# dorthy.net
KiCad netlist of a schematic drawn in EAGLE
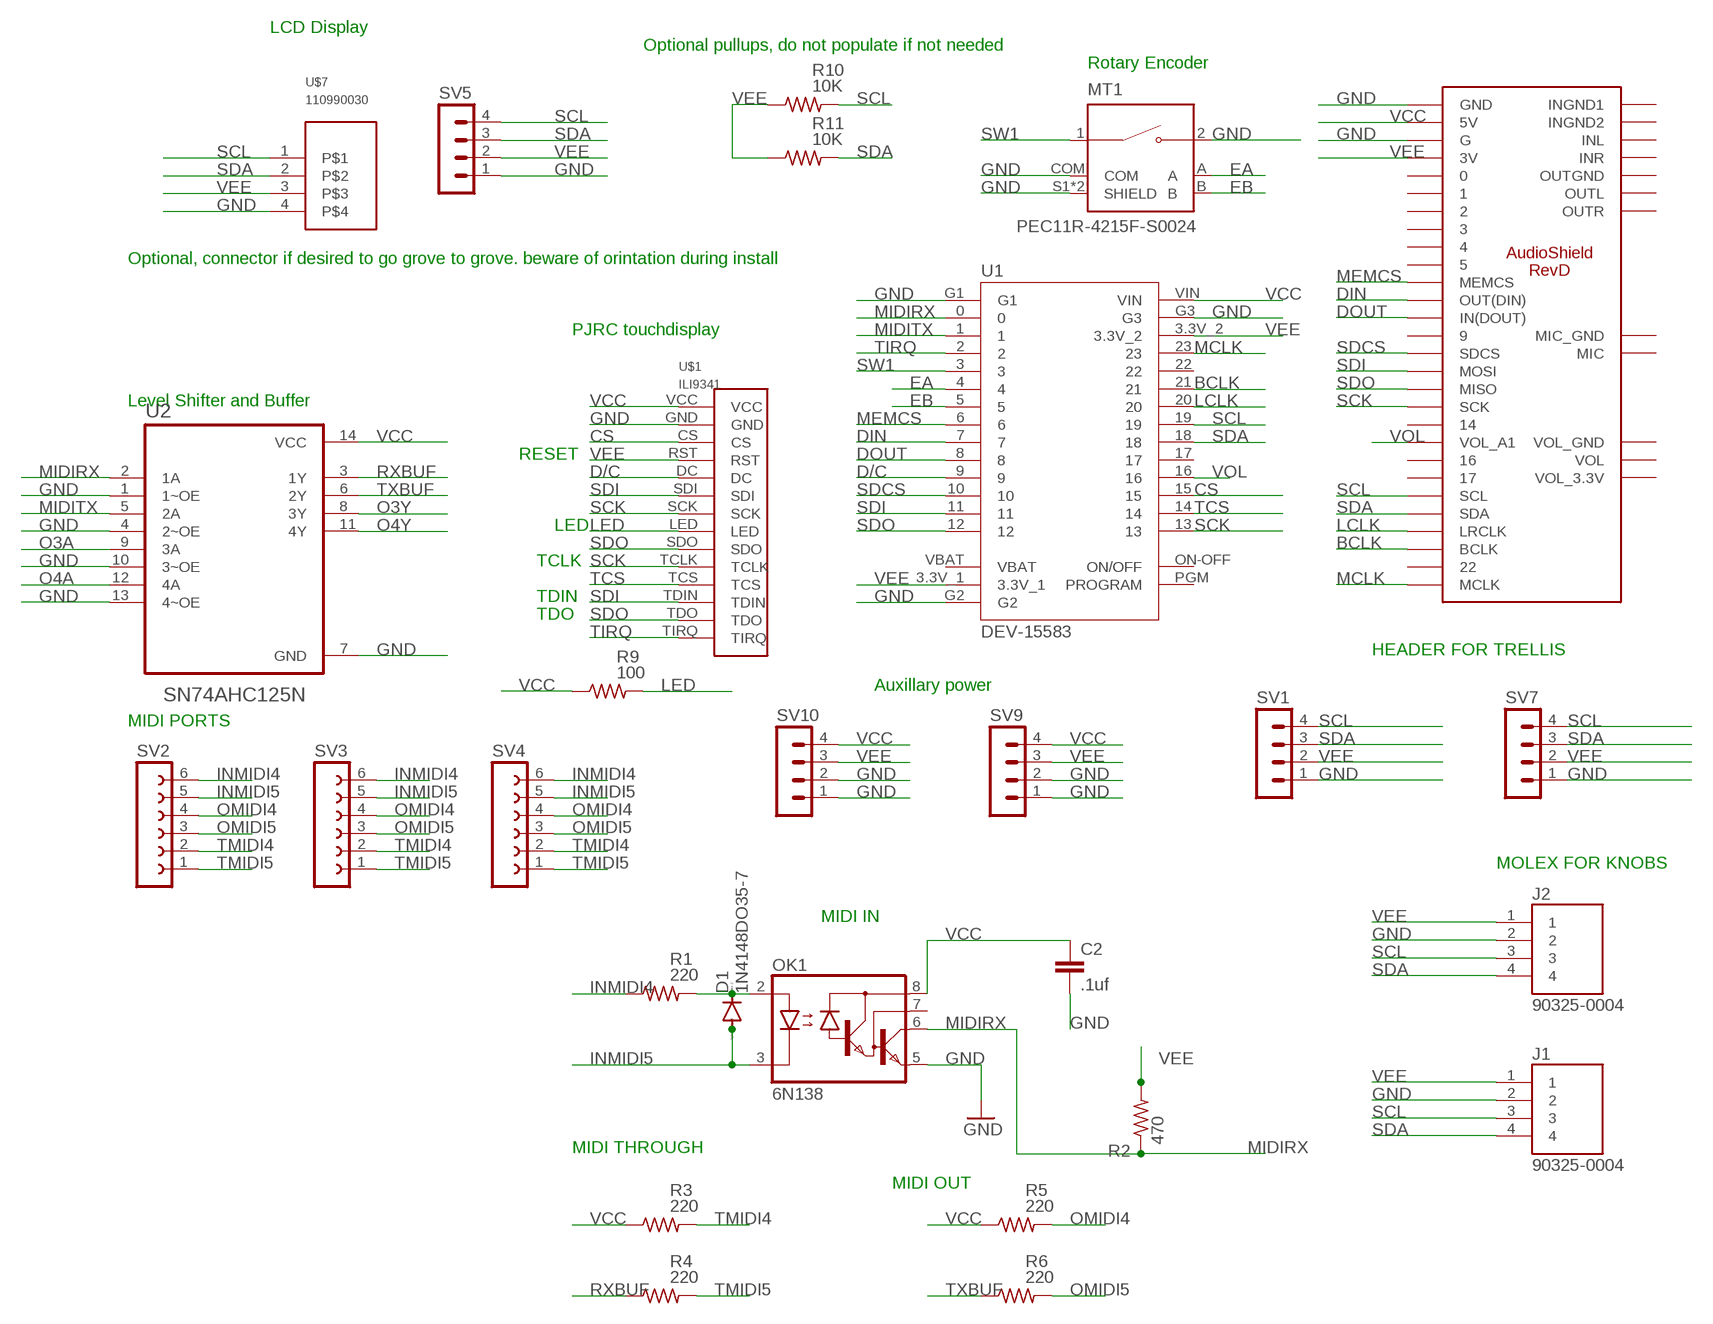
[diagram p0: schematic, sheet 1]

(export (version "E")
  (design (tool "Eeschema 10.0.6"))
  (components
    (comp (ref "C2")
      (value ".1uf")
      (footprint "eagle-import:C5B3.5")
      (libsource (lib "eagle-import") (part "C5/3.5"))
    )
    (comp (ref "D1")
      (value "1N4148DO35-7")
      (footprint "eagle-import:DO35-7")
      (libsource (lib "eagle-import") (part "1N4148DO35-7"))
    )
    (comp (ref "J1")
      (value "90325-0004")
      (footprint "eagle-import:MOLEX_90325-0004")
      (fields (field (name "MF") "Molex"))
      (libsource (lib "eagle-import") (part "90325-0004"))
    )
    (comp (ref "J2")
      (value "90325-0004")
      (footprint "eagle-import:MOLEX_90325-0004")
      (fields (field (name "MF") "Molex"))
      (libsource (lib "eagle-import") (part "90325-0004"))
    )
    (comp (ref "MT1")
      (value "PEC11R-4215F-S0024")
      (footprint "eagle-import:XDCR_PEC11R-4215F-S0024")
      (fields (field (name "MF") "Bourns"))
      (libsource (lib "eagle-import") (part "PEC11R-4215F-S0024"))
    )
    (comp (ref "OK1")
      (value "6N138")
      (footprint "eagle-import:DIL08")
      (fields (field (name "MF") "VISHAY/TELEFUNKEN"))
      (libsource (lib "eagle-import") (part "6N138"))
    )
    (comp (ref "R1")
      (value "220")
      (footprint "eagle-import:0207_10")
      (libsource (lib "eagle-import") (part "R-US_0207/10"))
    )
    (comp (ref "R2")
      (value "470")
      (footprint "eagle-import:0207_10")
      (libsource (lib "eagle-import") (part "R-US_0207/10"))
    )
    (comp (ref "R3")
      (value "220")
      (footprint "eagle-import:0207_10")
      (libsource (lib "eagle-import") (part "R-US_0207/10"))
    )
    (comp (ref "R4")
      (value "220")
      (footprint "eagle-import:0207_10")
      (libsource (lib "eagle-import") (part "R-US_0207/10"))
    )
    (comp (ref "R5")
      (value "220")
      (footprint "eagle-import:0207_10")
      (libsource (lib "eagle-import") (part "R-US_0207/10"))
    )
    (comp (ref "R6")
      (value "220")
      (footprint "eagle-import:0207_10")
      (libsource (lib "eagle-import") (part "R-US_0207/10"))
    )
    (comp (ref "R9")
      (value "100")
      (footprint "eagle-import:0207_10")
      (libsource (lib "eagle-import") (part "R-US_0207/10"))
    )
    (comp (ref "R10")
      (value "10K")
      (footprint "eagle-import:0207_10")
      (libsource (lib "eagle-import") (part "R-US_0207/10"))
    )
    (comp (ref "R11")
      (value "10K")
      (footprint "eagle-import:0207_10")
      (libsource (lib "eagle-import") (part "R-US_0207/10"))
    )
    (comp (ref "SV1")
      (value "MA04-1")
      (footprint "eagle-import:MA04-1")
      (libsource (lib "eagle-import") (part "MA04-1"))
    )
    (comp (ref "SV2")
      (value "FE06-1")
      (footprint "eagle-import:FE06")
      (libsource (lib "eagle-import") (part "FE06-1"))
    )
    (comp (ref "SV3")
      (value "FE06-1")
      (footprint "eagle-import:FE06")
      (libsource (lib "eagle-import") (part "FE06-1"))
    )
    (comp (ref "SV4")
      (value "FE06-1")
      (footprint "eagle-import:FE06")
      (libsource (lib "eagle-import") (part "FE06-1"))
    )
    (comp (ref "SV5")
      (value "MA04-1")
      (footprint "eagle-import:MA04-1")
      (libsource (lib "eagle-import") (part "MA04-1"))
    )
    (comp (ref "SV7")
      (value "MA04-1")
      (footprint "eagle-import:MA04-1")
      (libsource (lib "eagle-import") (part "MA04-1"))
    )
    (comp (ref "SV9")
      (value "MA04-1")
      (footprint "eagle-import:MA04-1")
      (libsource (lib "eagle-import") (part "MA04-1"))
    )
    (comp (ref "SV10")
      (value "MA04-1")
      (footprint "eagle-import:MA04-1")
      (libsource (lib "eagle-import") (part "MA04-1"))
    )
    (comp (ref "U$1")
      (value "ILI9341")
      (footprint "eagle-import:ILI9341")
      (libsource (lib "eagle-import") (part "ILI9341"))
    )
    (comp (ref "U$2")
      (value "AUDIOSHIELD-REVD")
      (footprint "eagle-import:AUDIOSHIELD-REVD")
      (libsource (lib "eagle-import") (part "AUDIOSHIELD-REVD"))
    )
    (comp (ref "U$7")
      (value "110990030")
      (footprint "eagle-import:110990030-VERTICAL-GROVE-CONNECTOR")
      (libsource (lib "eagle-import") (part "110990030"))
    )
    (comp (ref "U1")
      (value "DEV-15583")
      (footprint "eagle-import:MODULE_DEV-15583")
      (fields (field (name "MF") "SparkFun Electronics"))
      (libsource (lib "eagle-import") (part "DEV-15583"))
    )
    (comp (ref "U2")
      (value "SN74AHC125N")
      (footprint "eagle-import:DIP794W45P254L1969H508Q14")
      (fields (field (name "MF") "Texas Instruments"))
      (libsource (lib "eagle-import") (part "SN74AHC125N"))
    )
  )
  (nets
    (net (code "1") (name "/BCLK") (class "Default")
      (node (ref "U$2") (pin "21") (pinfunction "BCLK_21") (pintype "bidirectional"))
      (node (ref "U1") (pin "21") (pinfunction "21_21") (pintype "bidirectional"))
    )
    (net (code "2") (name "/CS") (class "Default")
      (node (ref "U$1") (pin "CS") (pinfunction "CS_CS") (pintype "bidirectional"))
      (node (ref "U1") (pin "15") (pinfunction "15_15") (pintype "bidirectional"))
    )
    (net (code "3") (name "/DIN") (class "Default")
      (node (ref "U$2") (pin "7") (pinfunction "OUT(DIN)_7") (pintype "bidirectional"))
      (node (ref "U1") (pin "7") (pinfunction "7_7") (pintype "bidirectional"))
    )
    (net (code "4") (name "/DOUT") (class "Default")
      (node (ref "U$2") (pin "8") (pinfunction "IN(DOUT)_8") (pintype "bidirectional"))
      (node (ref "U1") (pin "8") (pinfunction "8_8") (pintype "bidirectional"))
    )
    (net (code "5") (name "/D{slash}C") (class "Default")
      (node (ref "U$1") (pin "DC") (pinfunction "DC_DC") (pintype "bidirectional"))
      (node (ref "U1") (pin "9") (pinfunction "9_9") (pintype "bidirectional"))
    )
    (net (code "6") (name "/EA") (class "Default")
      (node (ref "MT1") (pin "A") (pinfunction "A_A") (pintype "passive"))
      (node (ref "U1") (pin "4") (pinfunction "4_4") (pintype "bidirectional"))
    )
    (net (code "7") (name "/EB") (class "Default")
      (node (ref "MT1") (pin "B") (pinfunction "B_B") (pintype "passive"))
      (node (ref "U1") (pin "5") (pinfunction "5_5") (pintype "bidirectional"))
    )
    (net (code "8") (name "/INMIDI4") (class "Default")
      (node (ref "R1") (pin "1") (pinfunction "1_1") (pintype "passive"))
      (node (ref "SV2") (pin "6") (pinfunction "6_6") (pintype "passive"))
      (node (ref "SV3") (pin "6") (pinfunction "6_6") (pintype "passive"))
      (node (ref "SV4") (pin "6") (pinfunction "6_6") (pintype "passive"))
    )
    (net (code "9") (name "/INMIDI5") (class "Default")
      (node (ref "D1") (pin "A") (pinfunction "A_A") (pintype "passive"))
      (node (ref "OK1") (pin "3") (pinfunction "C_3") (pintype "passive"))
      (node (ref "SV2") (pin "5") (pinfunction "5_5") (pintype "passive"))
      (node (ref "SV3") (pin "5") (pinfunction "5_5") (pintype "passive"))
      (node (ref "SV4") (pin "5") (pinfunction "5_5") (pintype "passive"))
    )
    (net (code "10") (name "/LCLK") (class "Default")
      (node (ref "U$2") (pin "20") (pinfunction "LRCLK_20") (pintype "bidirectional"))
      (node (ref "U1") (pin "20") (pinfunction "20_20") (pintype "bidirectional"))
    )
    (net (code "11") (name "/LED") (class "Default")
      (node (ref "R9") (pin "2") (pinfunction "2_2") (pintype "passive"))
      (node (ref "U$1") (pin "LED") (pinfunction "LED_LED") (pintype "bidirectional"))
    )
    (net (code "12") (name "/MCLK") (class "Default")
      (node (ref "U$2") (pin "23") (pinfunction "MCLK_23") (pintype "bidirectional"))
      (node (ref "U1") (pin "23") (pinfunction "23_23") (pintype "bidirectional"))
    )
    (net (code "13") (name "/MEMCS") (class "Default")
      (node (ref "U$2") (pin "6") (pinfunction "MEMCS_6") (pintype "bidirectional"))
      (node (ref "U1") (pin "6") (pinfunction "6_6") (pintype "bidirectional"))
    )
    (net (code "14") (name "/MIDIRX") (class "Default")
      (node (ref "OK1") (pin "6") (pinfunction "VO_6") (pintype "passive"))
      (node (ref "R2") (pin "1") (pinfunction "1_1") (pintype "passive"))
      (node (ref "U1") (pin "0") (pinfunction "0_0") (pintype "bidirectional"))
      (node (ref "U2") (pin "2") (pinfunction "1A_2") (pintype "input"))
    )
    (net (code "15") (name "/MIDITX") (class "Default")
      (node (ref "U1") (pin "1") (pinfunction "1_1") (pintype "bidirectional"))
      (node (ref "U2") (pin "5") (pinfunction "2A_5") (pintype "input"))
    )
    (net (code "16") (name "/O3A") (class "Default")
      (node (ref "U2") (pin "9") (pinfunction "3A_9") (pintype "input"))
    )
    (net (code "17") (name "/O3Y") (class "Default")
      (node (ref "U2") (pin "8") (pinfunction "3Y_8") (pintype "output"))
    )
    (net (code "18") (name "/O4A") (class "Default")
      (node (ref "U2") (pin "12") (pinfunction "4A_12") (pintype "input"))
    )
    (net (code "19") (name "/O4Y") (class "Default")
      (node (ref "U2") (pin "11") (pinfunction "4Y_11") (pintype "output"))
    )
    (net (code "20") (name "/OMIDI4") (class "Default")
      (node (ref "R5") (pin "2") (pinfunction "2_2") (pintype "passive"))
      (node (ref "SV2") (pin "4") (pinfunction "4_4") (pintype "passive"))
      (node (ref "SV3") (pin "4") (pinfunction "4_4") (pintype "passive"))
      (node (ref "SV4") (pin "4") (pinfunction "4_4") (pintype "passive"))
    )
    (net (code "21") (name "/OMIDI5") (class "Default")
      (node (ref "R6") (pin "2") (pinfunction "2_2") (pintype "passive"))
      (node (ref "SV2") (pin "3") (pinfunction "3_3") (pintype "passive"))
      (node (ref "SV3") (pin "3") (pinfunction "3_3") (pintype "passive"))
      (node (ref "SV4") (pin "3") (pinfunction "3_3") (pintype "passive"))
    )
    (net (code "22") (name "/RXBUF") (class "Default")
      (node (ref "R4") (pin "1") (pinfunction "1_1") (pintype "passive"))
      (node (ref "U2") (pin "3") (pinfunction "1Y_3") (pintype "output"))
    )
    (net (code "23") (name "/SCK") (class "Default")
      (node (ref "U$1") (pin "SCK") (pinfunction "SCK_SCK") (pintype "bidirectional"))
      (node (ref "U$1") (pin "TCLK") (pinfunction "TCLK_TCLK") (pintype "bidirectional"))
      (node (ref "U$2") (pin "13") (pinfunction "SCK_13") (pintype "bidirectional"))
      (node (ref "U1") (pin "13") (pinfunction "13_13") (pintype "bidirectional"))
    )
    (net (code "24") (name "/SCL") (class "Default")
      (node (ref "J1") (pin "3") (pinfunction "3_3") (pintype "passive"))
      (node (ref "J2") (pin "3") (pinfunction "3_3") (pintype "passive"))
      (node (ref "R10") (pin "2") (pinfunction "2_2") (pintype "passive"))
      (node (ref "SV1") (pin "4") (pinfunction "4_4") (pintype "passive"))
      (node (ref "SV5") (pin "4") (pinfunction "4_4") (pintype "passive"))
      (node (ref "SV7") (pin "4") (pinfunction "4_4") (pintype "passive"))
      (node (ref "U$2") (pin "19") (pinfunction "SCL_19") (pintype "bidirectional"))
      (node (ref "U$7") (pin "1") (pinfunction "P$1_1") (pintype "bidirectional"))
      (node (ref "U1") (pin "19") (pinfunction "19_19") (pintype "bidirectional"))
    )
    (net (code "25") (name "/SDA") (class "Default")
      (node (ref "J1") (pin "4") (pinfunction "4_4") (pintype "passive"))
      (node (ref "J2") (pin "4") (pinfunction "4_4") (pintype "passive"))
      (node (ref "R11") (pin "2") (pinfunction "2_2") (pintype "passive"))
      (node (ref "SV1") (pin "3") (pinfunction "3_3") (pintype "passive"))
      (node (ref "SV5") (pin "3") (pinfunction "3_3") (pintype "passive"))
      (node (ref "SV7") (pin "3") (pinfunction "3_3") (pintype "passive"))
      (node (ref "U$2") (pin "18") (pinfunction "SDA_18") (pintype "bidirectional"))
      (node (ref "U$7") (pin "2") (pinfunction "P$2_2") (pintype "bidirectional"))
      (node (ref "U1") (pin "18") (pinfunction "18_18") (pintype "bidirectional"))
    )
    (net (code "26") (name "/SDCS") (class "Default")
      (node (ref "U$2") (pin "10") (pinfunction "SDCS_10") (pintype "bidirectional"))
      (node (ref "U1") (pin "10") (pinfunction "10_10") (pintype "bidirectional"))
    )
    (net (code "27") (name "/SDI") (class "Default")
      (node (ref "U$1") (pin "SDI") (pinfunction "SDI_SDI") (pintype "bidirectional"))
      (node (ref "U$1") (pin "TDIN") (pinfunction "TDIN_TDIN") (pintype "bidirectional"))
      (node (ref "U$2") (pin "11") (pinfunction "MOSI_11") (pintype "bidirectional"))
      (node (ref "U1") (pin "11") (pinfunction "11_11") (pintype "bidirectional"))
    )
    (net (code "28") (name "/SDO") (class "Default")
      (node (ref "U$1") (pin "SDO") (pinfunction "SDO_SDO") (pintype "bidirectional"))
      (node (ref "U$1") (pin "TDO") (pinfunction "TDO_TDO") (pintype "bidirectional"))
      (node (ref "U$2") (pin "12") (pinfunction "MISO_12") (pintype "bidirectional"))
      (node (ref "U1") (pin "12") (pinfunction "12_12") (pintype "bidirectional"))
    )
    (net (code "29") (name "/SW1") (class "Default")
      (node (ref "MT1") (pin "1") (pinfunction "1_1") (pintype "passive"))
      (node (ref "U1") (pin "3") (pinfunction "3_3") (pintype "bidirectional"))
    )
    (net (code "30") (name "/TCS") (class "Default")
      (node (ref "U$1") (pin "TCS") (pinfunction "TCS_TCS") (pintype "bidirectional"))
      (node (ref "U1") (pin "14") (pinfunction "14_14") (pintype "bidirectional"))
    )
    (net (code "31") (name "/TIRQ") (class "Default")
      (node (ref "U$1") (pin "TIRQ") (pinfunction "TIRQ_TIRQ") (pintype "bidirectional"))
      (node (ref "U1") (pin "2") (pinfunction "2_2") (pintype "bidirectional"))
    )
    (net (code "32") (name "/TMIDI4") (class "Default")
      (node (ref "R3") (pin "2") (pinfunction "2_2") (pintype "passive"))
      (node (ref "SV2") (pin "2") (pinfunction "2_2") (pintype "passive"))
      (node (ref "SV3") (pin "2") (pinfunction "2_2") (pintype "passive"))
      (node (ref "SV4") (pin "2") (pinfunction "2_2") (pintype "passive"))
    )
    (net (code "33") (name "/TMIDI5") (class "Default")
      (node (ref "R4") (pin "2") (pinfunction "2_2") (pintype "passive"))
      (node (ref "SV2") (pin "1") (pinfunction "1_1") (pintype "passive"))
      (node (ref "SV3") (pin "1") (pinfunction "1_1") (pintype "passive"))
      (node (ref "SV4") (pin "1") (pinfunction "1_1") (pintype "passive"))
    )
    (net (code "34") (name "/TXBUF") (class "Default")
      (node (ref "R6") (pin "1") (pinfunction "1_1") (pintype "passive"))
      (node (ref "U2") (pin "6") (pinfunction "2Y_6") (pintype "output"))
    )
    (net (code "35") (name "/VBAT") (class "Default")
      (node (ref "U1") (pin "VBAT") (pinfunction "VBAT_VBAT") (pintype "power_in"))
    )
    (net (code "36") (name "/VCC") (class "Default")
      (node (ref "C2") (pin "1") (pinfunction "1_1") (pintype "passive"))
      (node (ref "OK1") (pin "8") (pinfunction "VCC_8") (pintype "passive"))
      (node (ref "R3") (pin "1") (pinfunction "1_1") (pintype "passive"))
      (node (ref "R5") (pin "1") (pinfunction "1_1") (pintype "passive"))
      (node (ref "R9") (pin "1") (pinfunction "1_1") (pintype "passive"))
      (node (ref "SV10") (pin "4") (pinfunction "4_4") (pintype "passive"))
      (node (ref "SV9") (pin "4") (pinfunction "4_4") (pintype "passive"))
      (node (ref "U$1") (pin "VCC") (pinfunction "VCC_VCC") (pintype "bidirectional"))
      (node (ref "U$2") (pin "5V") (pinfunction "5V_5V") (pintype "bidirectional"))
      (node (ref "U1") (pin "VIN") (pinfunction "VIN_VIN") (pintype "power_in"))
      (node (ref "U2") (pin "14") (pinfunction "VCC_14") (pintype "power_in"))
    )
    (net (code "37") (name "/VEE") (class "Default")
      (node (ref "J1") (pin "1") (pinfunction "1_1") (pintype "passive"))
      (node (ref "J2") (pin "1") (pinfunction "1_1") (pintype "passive"))
      (node (ref "R10") (pin "1") (pinfunction "1_1") (pintype "passive"))
      (node (ref "R11") (pin "1") (pinfunction "1_1") (pintype "passive"))
      (node (ref "R2") (pin "2") (pinfunction "2_2") (pintype "passive"))
      (node (ref "SV1") (pin "2") (pinfunction "2_2") (pintype "passive"))
      (node (ref "SV10") (pin "3") (pinfunction "3_3") (pintype "passive"))
      (node (ref "SV5") (pin "2") (pinfunction "2_2") (pintype "passive"))
      (node (ref "SV7") (pin "2") (pinfunction "2_2") (pintype "passive"))
      (node (ref "SV9") (pin "3") (pinfunction "3_3") (pintype "passive"))
      (node (ref "U$1") (pin "RST") (pinfunction "RST_RST") (pintype "bidirectional"))
      (node (ref "U$2") (pin "3V") (pinfunction "3V_3V") (pintype "bidirectional"))
      (node (ref "U$7") (pin "3") (pinfunction "P$3_3") (pintype "bidirectional"))
      (node (ref "U1") (pin "3.3V_1") (pinfunction "3.3V_1_3.3V_1") (pintype "power_in"))
      (node (ref "U1") (pin "3.3V_2") (pinfunction "3.3V_2_3.3V_2") (pintype "power_in"))
    )
    (net (code "38") (name "/VOL") (class "Default")
      (node (ref "U$2") (pin "15") (pinfunction "VOL_A1_15") (pintype "bidirectional"))
      (node (ref "U1") (pin "16") (pinfunction "16_16") (pintype "bidirectional"))
    )
    (net (code "39") (name "GND") (class "Default")
      (node (ref "C2") (pin "2") (pinfunction "2_2") (pintype "passive"))
      (node (ref "J1") (pin "2") (pinfunction "2_2") (pintype "passive"))
      (node (ref "J2") (pin "2") (pinfunction "2_2") (pintype "passive"))
      (node (ref "MT1") (pin "2") (pinfunction "2_2") (pintype "passive"))
      (node (ref "MT1") (pin "COM") (pinfunction "COM_COM") (pintype "passive"))
      (node (ref "MT1") (pin "S1") (pinfunction "SHIELD_S1") (pintype "passive"))
      (node (ref "MT1") (pin "S2") (pinfunction "SHIELD_S2") (pintype "passive"))
      (node (ref "OK1") (pin "5") (pinfunction "GND_5") (pintype "passive"))
      (node (ref "SV1") (pin "1") (pinfunction "1_1") (pintype "passive"))
      (node (ref "SV10") (pin "1") (pinfunction "1_1") (pintype "passive"))
      (node (ref "SV10") (pin "2") (pinfunction "2_2") (pintype "passive"))
      (node (ref "SV5") (pin "1") (pinfunction "1_1") (pintype "passive"))
      (node (ref "SV7") (pin "1") (pinfunction "1_1") (pintype "passive"))
      (node (ref "SV9") (pin "1") (pinfunction "1_1") (pintype "passive"))
      (node (ref "SV9") (pin "2") (pinfunction "2_2") (pintype "passive"))
      (node (ref "U$1") (pin "GND") (pinfunction "GND_GND") (pintype "bidirectional"))
      (node (ref "U$2") (pin "G") (pinfunction "G_G") (pintype "bidirectional"))
      (node (ref "U$2") (pin "GND") (pinfunction "GND_GND") (pintype "bidirectional"))
      (node (ref "U$7") (pin "4") (pinfunction "P$4_4") (pintype "bidirectional"))
      (node (ref "U1") (pin "G1") (pinfunction "G1_G1") (pintype "power_in"))
      (node (ref "U1") (pin "G2") (pinfunction "G2_G2") (pintype "power_in"))
      (node (ref "U1") (pin "G3") (pinfunction "G3_G3") (pintype "power_in"))
      (node (ref "U2") (pin "1") (pinfunction "1~{OE}_1") (pintype "input"))
      (node (ref "U2") (pin "10") (pinfunction "3~{OE}_10") (pintype "input"))
      (node (ref "U2") (pin "13") (pinfunction "4~{OE}_13") (pintype "input"))
      (node (ref "U2") (pin "4") (pinfunction "2~{OE}_4") (pintype "input"))
      (node (ref "U2") (pin "7") (pinfunction "GND_7") (pintype "power_in"))
    )
    (net (code "40") (name "Net-(OK1-A)") (class "Default")
      (node (ref "D1") (pin "C") (pinfunction "C_C") (pintype "passive"))
      (node (ref "OK1") (pin "2") (pinfunction "A_2") (pintype "passive"))
      (node (ref "R1") (pin "2") (pinfunction "2_2") (pintype "passive"))
    )
    (net (code "41") (name "unconnected-(OK1-VB-Pad7)") (class "Default")
      (node (ref "OK1") (pin "7") (pinfunction "VB_7") (pintype "passive"))
    )
    (net (code "42") (name "unconnected-(U$2-MIC_GND-PadGND_MIC)") (class "Default")
      (node (ref "U$2") (pin "GND_MIC") (pinfunction "MIC_GND_GND_MIC") (pintype "bidirectional"))
    )
    (net (code "43") (name "unconnected-(U$2-Pad0)") (class "Default")
      (node (ref "U$2") (pin "0") (pinfunction "0_0") (pintype "bidirectional"))
    )
    (net (code "44") (name "unconnected-(U$2-Pad1)") (class "Default")
      (node (ref "U$2") (pin "1") (pinfunction "1_1") (pintype "bidirectional"))
    )
    (net (code "45") (name "unconnected-(U$2-Pad2)") (class "Default")
      (node (ref "U$2") (pin "2") (pinfunction "2_2") (pintype "bidirectional"))
    )
    (net (code "46") (name "unconnected-(U$2-Pad3)") (class "Default")
      (node (ref "U$2") (pin "3") (pinfunction "3_3") (pintype "bidirectional"))
    )
    (net (code "47") (name "unconnected-(U$2-Pad4)") (class "Default")
      (node (ref "U$2") (pin "4") (pinfunction "4_4") (pintype "bidirectional"))
    )
    (net (code "48") (name "unconnected-(U$2-Pad5)") (class "Default")
      (node (ref "U$2") (pin "5") (pinfunction "5_5") (pintype "bidirectional"))
    )
    (net (code "49") (name "unconnected-(U$2-Pad9)") (class "Default")
      (node (ref "U$2") (pin "9") (pinfunction "9_9") (pintype "bidirectional"))
    )
    (net (code "50") (name "unconnected-(U$2-Pad14)") (class "Default")
      (node (ref "U$2") (pin "14") (pinfunction "14_14") (pintype "bidirectional"))
    )
    (net (code "51") (name "unconnected-(U$2-Pad16)") (class "Default")
      (node (ref "U$2") (pin "16") (pinfunction "16_16") (pintype "bidirectional"))
    )
    (net (code "52") (name "unconnected-(U$2-Pad17)") (class "Default")
      (node (ref "U$2") (pin "17") (pinfunction "17_17") (pintype "bidirectional"))
    )
    (net (code "53") (name "unconnected-(U$2-Pad22)") (class "Default")
      (node (ref "U$2") (pin "22") (pinfunction "22_22") (pintype "bidirectional"))
    )
    (net (code "54") (name "unconnected-(U$2-PadINGND1)") (class "Default")
      (node (ref "U$2") (pin "INGND1") (pinfunction "INGND1_INGND1") (pintype "bidirectional"))
    )
    (net (code "55") (name "unconnected-(U$2-PadINGND2)") (class "Default")
      (node (ref "U$2") (pin "INGND2") (pinfunction "INGND2_INGND2") (pintype "bidirectional"))
    )
    (net (code "56") (name "unconnected-(U$2-PadINL)") (class "Default")
      (node (ref "U$2") (pin "INL") (pinfunction "INL_INL") (pintype "input"))
    )
    (net (code "57") (name "unconnected-(U$2-PadINR)") (class "Default")
      (node (ref "U$2") (pin "INR") (pinfunction "INR_INR") (pintype "input"))
    )
    (net (code "58") (name "unconnected-(U$2-PadMIC)") (class "Default")
      (node (ref "U$2") (pin "MIC") (pinfunction "MIC_MIC") (pintype "input"))
    )
    (net (code "59") (name "unconnected-(U$2-PadOUTGND)") (class "Default")
      (node (ref "U$2") (pin "OUTGND") (pinfunction "OUTGND_OUTGND") (pintype "bidirectional"))
    )
    (net (code "60") (name "unconnected-(U$2-PadOUTL)") (class "Default")
      (node (ref "U$2") (pin "OUTL") (pinfunction "OUTL_OUTL") (pintype "output"))
    )
    (net (code "61") (name "unconnected-(U$2-PadOUTR)") (class "Default")
      (node (ref "U$2") (pin "OUTR") (pinfunction "OUTR_OUTR") (pintype "output"))
    )
    (net (code "62") (name "unconnected-(U$2-PadVOL)") (class "Default")
      (node (ref "U$2") (pin "VOL") (pinfunction "VOL_VOL") (pintype "input"))
    )
    (net (code "63") (name "unconnected-(U$2-PadVOL_3.3V)") (class "Default")
      (node (ref "U$2") (pin "VOL_3.3V") (pinfunction "VOL_3.3V_VOL_3.3V") (pintype "bidirectional"))
    )
    (net (code "64") (name "unconnected-(U$2-PadVOL_GND)") (class "Default")
      (node (ref "U$2") (pin "VOL_GND") (pinfunction "VOL_GND_VOL_GND") (pintype "bidirectional"))
    )
    (net (code "65") (name "unconnected-(U1-ON{slash}OFF-PadON-OFF)") (class "Default")
      (node (ref "U1") (pin "ON-OFF") (pinfunction "ON/OFF_ON-OFF") (pintype "bidirectional"))
    )
    (net (code "66") (name "unconnected-(U1-PROGRAM-PadPGM)") (class "Default")
      (node (ref "U1") (pin "PGM") (pinfunction "PROGRAM_PGM") (pintype "bidirectional"))
    )
    (net (code "67") (name "unconnected-(U1-Pad17)") (class "Default")
      (node (ref "U1") (pin "17") (pinfunction "17_17") (pintype "bidirectional"))
    )
    (net (code "68") (name "unconnected-(U1-Pad22)") (class "Default")
      (node (ref "U1") (pin "22") (pinfunction "22_22") (pintype "bidirectional"))
    )
  )
)
